# ioThing-schematic.net
KiCad netlist of a schematic drawn in EAGLE
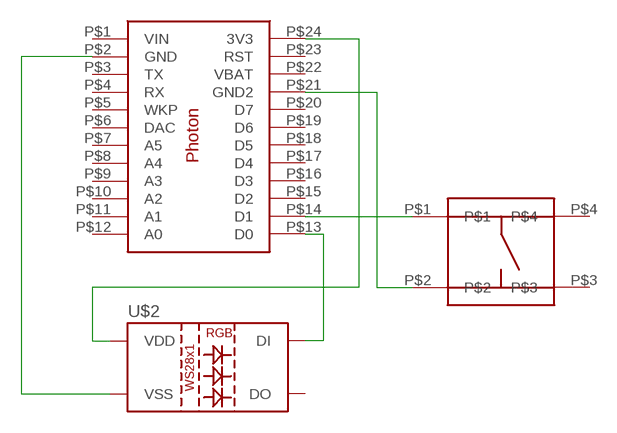
[diagram p0: schematic, sheet 1]

(export (version "E")
  (design (tool "Eeschema 10.0.6"))
  (components
    (comp (ref "U$1")
      (value "PHOTON")
      (footprint "eagle-import:PHOTON")
      (libsource (lib "eagle-import") (part "PHOTON"))
    )
    (comp (ref "U$2")
      (value "5MM-NEOPIXEL")
      (footprint "eagle-import:T1-3_4-LED")
      (libsource (lib "eagle-import") (part "5MM-NEOPIXEL"))
    )
    (comp (ref "U$3")
      (value "TACTILE_SWITCH")
      (footprint "eagle-import:TACTILE_SWITCH")
      (libsource (lib "eagle-import") (part "TACTILE_SWITCH"))
    )
  )
  (nets
    (net (code "1") (name "Net-(U$1-3V3)") (class "Default")
      (node (ref "U$1") (pin "P$24") (pinfunction "3V3_P$24") (pintype "bidirectional"))
      (node (ref "U$2") (pin "P$2") (pinfunction "VDD_P$2") (pintype "bidirectional"))
    )
    (net (code "2") (name "Net-(U$1-D0)") (class "Default")
      (node (ref "U$1") (pin "P$13") (pinfunction "D0_P$13") (pintype "bidirectional"))
      (node (ref "U$2") (pin "P$1") (pinfunction "DI_P$1") (pintype "bidirectional"))
    )
    (net (code "3") (name "Net-(U$1-D1)") (class "Default")
      (node (ref "U$1") (pin "P$14") (pinfunction "D1_P$14") (pintype "bidirectional"))
      (node (ref "U$3") (pin "P$1") (pinfunction "P$1_P$1") (pintype "bidirectional"))
    )
    (net (code "4") (name "Net-(U$1-GND)") (class "Default")
      (node (ref "U$1") (pin "P$2") (pinfunction "GND_P$2") (pintype "bidirectional"))
      (node (ref "U$2") (pin "P$3") (pinfunction "VSS_P$3") (pintype "bidirectional"))
    )
    (net (code "5") (name "Net-(U$1-GND2)") (class "Default")
      (node (ref "U$1") (pin "P$21") (pinfunction "GND2_P$21") (pintype "bidirectional"))
      (node (ref "U$3") (pin "P$2") (pinfunction "P$2_P$2") (pintype "bidirectional"))
    )
    (net (code "6") (name "unconnected-(U$1-A0-PadP$12)") (class "Default")
      (node (ref "U$1") (pin "P$12") (pinfunction "A0_P$12") (pintype "bidirectional"))
    )
    (net (code "7") (name "unconnected-(U$1-A1-PadP$11)") (class "Default")
      (node (ref "U$1") (pin "P$11") (pinfunction "A1_P$11") (pintype "bidirectional"))
    )
    (net (code "8") (name "unconnected-(U$1-A2-PadP$10)") (class "Default")
      (node (ref "U$1") (pin "P$10") (pinfunction "A2_P$10") (pintype "bidirectional"))
    )
    (net (code "9") (name "unconnected-(U$1-A3-PadP$9)") (class "Default")
      (node (ref "U$1") (pin "P$9") (pinfunction "A3_P$9") (pintype "bidirectional"))
    )
    (net (code "10") (name "unconnected-(U$1-A4-PadP$8)") (class "Default")
      (node (ref "U$1") (pin "P$8") (pinfunction "A4_P$8") (pintype "bidirectional"))
    )
    (net (code "11") (name "unconnected-(U$1-A5-PadP$7)") (class "Default")
      (node (ref "U$1") (pin "P$7") (pinfunction "A5_P$7") (pintype "bidirectional"))
    )
    (net (code "12") (name "unconnected-(U$1-D2-PadP$15)") (class "Default")
      (node (ref "U$1") (pin "P$15") (pinfunction "D2_P$15") (pintype "bidirectional"))
    )
    (net (code "13") (name "unconnected-(U$1-D3-PadP$16)") (class "Default")
      (node (ref "U$1") (pin "P$16") (pinfunction "D3_P$16") (pintype "bidirectional"))
    )
    (net (code "14") (name "unconnected-(U$1-D4-PadP$17)") (class "Default")
      (node (ref "U$1") (pin "P$17") (pinfunction "D4_P$17") (pintype "bidirectional"))
    )
    (net (code "15") (name "unconnected-(U$1-D5-PadP$18)") (class "Default")
      (node (ref "U$1") (pin "P$18") (pinfunction "D5_P$18") (pintype "bidirectional"))
    )
    (net (code "16") (name "unconnected-(U$1-D6-PadP$19)") (class "Default")
      (node (ref "U$1") (pin "P$19") (pinfunction "D6_P$19") (pintype "bidirectional"))
    )
    (net (code "17") (name "unconnected-(U$1-D7-PadP$20)") (class "Default")
      (node (ref "U$1") (pin "P$20") (pinfunction "D7_P$20") (pintype "bidirectional"))
    )
    (net (code "18") (name "unconnected-(U$1-DAC-PadP$6)") (class "Default")
      (node (ref "U$1") (pin "P$6") (pinfunction "DAC_P$6") (pintype "bidirectional"))
    )
    (net (code "19") (name "unconnected-(U$1-RST-PadP$23)") (class "Default")
      (node (ref "U$1") (pin "P$23") (pinfunction "RST_P$23") (pintype "bidirectional"))
    )
    (net (code "20") (name "unconnected-(U$1-RX-PadP$4)") (class "Default")
      (node (ref "U$1") (pin "P$4") (pinfunction "RX_P$4") (pintype "bidirectional"))
    )
    (net (code "21") (name "unconnected-(U$1-TX-PadP$3)") (class "Default")
      (node (ref "U$1") (pin "P$3") (pinfunction "TX_P$3") (pintype "bidirectional"))
    )
    (net (code "22") (name "unconnected-(U$1-VBAT-PadP$22)") (class "Default")
      (node (ref "U$1") (pin "P$22") (pinfunction "VBAT_P$22") (pintype "bidirectional"))
    )
    (net (code "23") (name "unconnected-(U$1-VIN-PadP$1)") (class "Default")
      (node (ref "U$1") (pin "P$1") (pinfunction "VIN_P$1") (pintype "bidirectional"))
    )
    (net (code "24") (name "unconnected-(U$1-WKP-PadP$5)") (class "Default")
      (node (ref "U$1") (pin "P$5") (pinfunction "WKP_P$5") (pintype "bidirectional"))
    )
    (net (code "25") (name "unconnected-(U$2-DO-PadP$4)") (class "Default")
      (node (ref "U$2") (pin "P$4") (pinfunction "DO_P$4") (pintype "bidirectional"))
    )
    (net (code "26") (name "unconnected-(U$3-PadP$3)") (class "Default")
      (node (ref "U$3") (pin "P$3") (pinfunction "P$3_P$3") (pintype "bidirectional"))
    )
    (net (code "27") (name "unconnected-(U$3-PadP$4)") (class "Default")
      (node (ref "U$3") (pin "P$4") (pinfunction "P$4_P$4") (pintype "bidirectional"))
    )
  )
)
